# Tuan_Hub.net
KiCad netlist of a schematic drawn in Altium Designer
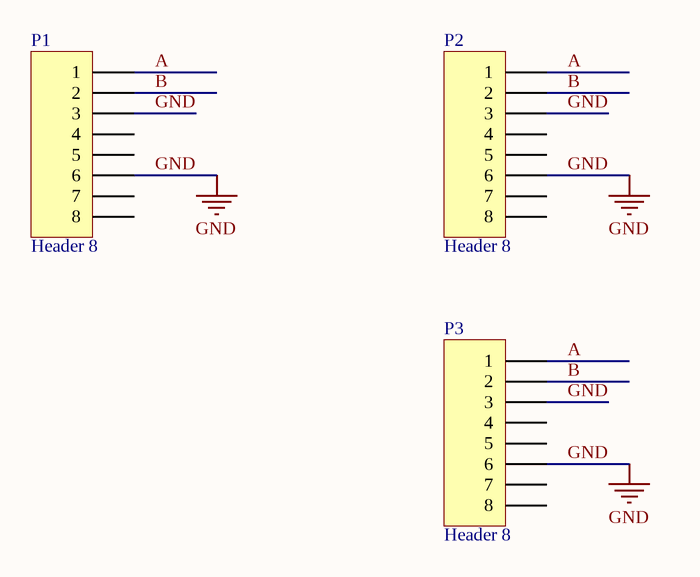
[diagram p0: Tuan_Hub.SchDoc]

(export (version "E")
  (design (tool "Eeschema 10.0.6"))
  (components
    (comp (ref "P1")
      (value "Header 8")
      (footprint "RJ11")
      (description "Header, 8-Pin")
      (fields (field (name "PUBLISHER") "Altium Limited"))
      (libsource (lib "THG") (part "Header 8"))
    )
    (comp (ref "P2")
      (value "Header 8")
      (footprint "RJ11")
      (description "Header, 8-Pin")
      (fields (field (name "PUBLISHER") "Altium Limited"))
      (libsource (lib "THG") (part "Header 8"))
    )
    (comp (ref "P3")
      (value "Header 8")
      (footprint "RJ11")
      (description "Header, 8-Pin")
      (fields (field (name "PUBLISHER") "Altium Limited"))
      (libsource (lib "THG") (part "Header 8"))
    )
  )
  (nets
    (net (code "1") (name "/A") (class "Default")
      (node (ref "P1") (pin "1") (pinfunction "1_1") (pintype "passive"))
      (node (ref "P2") (pin "1") (pinfunction "1_1") (pintype "passive"))
      (node (ref "P3") (pin "1") (pinfunction "1_1") (pintype "passive"))
    )
    (net (code "2") (name "/B") (class "Default")
      (node (ref "P1") (pin "2") (pinfunction "2_2") (pintype "passive"))
      (node (ref "P2") (pin "2") (pinfunction "2_2") (pintype "passive"))
      (node (ref "P3") (pin "2") (pinfunction "2_2") (pintype "passive"))
    )
    (net (code "3") (name "GND") (class "Default")
      (node (ref "P1") (pin "3") (pinfunction "3_3") (pintype "passive"))
      (node (ref "P1") (pin "6") (pinfunction "6_6") (pintype "passive"))
      (node (ref "P2") (pin "3") (pinfunction "3_3") (pintype "passive"))
      (node (ref "P2") (pin "6") (pinfunction "6_6") (pintype "passive"))
      (node (ref "P3") (pin "3") (pinfunction "3_3") (pintype "passive"))
      (node (ref "P3") (pin "6") (pinfunction "6_6") (pintype "passive"))
    )
    (net (code "4") (name "unconnected-(P1-Pad4)") (class "Default")
      (node (ref "P1") (pin "4") (pinfunction "4_4") (pintype "passive"))
    )
    (net (code "5") (name "unconnected-(P1-Pad5)") (class "Default")
      (node (ref "P1") (pin "5") (pinfunction "5_5") (pintype "passive"))
    )
    (net (code "6") (name "unconnected-(P1-Pad7)") (class "Default")
      (node (ref "P1") (pin "7") (pinfunction "7_7") (pintype "passive"))
    )
    (net (code "7") (name "unconnected-(P1-Pad8)") (class "Default")
      (node (ref "P1") (pin "8") (pinfunction "8_8") (pintype "passive"))
    )
    (net (code "8") (name "unconnected-(P2-Pad4)") (class "Default")
      (node (ref "P2") (pin "4") (pinfunction "4_4") (pintype "passive"))
    )
    (net (code "9") (name "unconnected-(P2-Pad5)") (class "Default")
      (node (ref "P2") (pin "5") (pinfunction "5_5") (pintype "passive"))
    )
    (net (code "10") (name "unconnected-(P2-Pad7)") (class "Default")
      (node (ref "P2") (pin "7") (pinfunction "7_7") (pintype "passive"))
    )
    (net (code "11") (name "unconnected-(P2-Pad8)") (class "Default")
      (node (ref "P2") (pin "8") (pinfunction "8_8") (pintype "passive"))
    )
    (net (code "12") (name "unconnected-(P3-Pad4)") (class "Default")
      (node (ref "P3") (pin "4") (pinfunction "4_4") (pintype "passive"))
    )
    (net (code "13") (name "unconnected-(P3-Pad5)") (class "Default")
      (node (ref "P3") (pin "5") (pinfunction "5_5") (pintype "passive"))
    )
    (net (code "14") (name "unconnected-(P3-Pad7)") (class "Default")
      (node (ref "P3") (pin "7") (pinfunction "7_7") (pintype "passive"))
    )
    (net (code "15") (name "unconnected-(P3-Pad8)") (class "Default")
      (node (ref "P3") (pin "8") (pinfunction "8_8") (pintype "passive"))
    )
  )
)
